# 05B-001.net
KiCad netlist of a schematic drawn in EAGLE
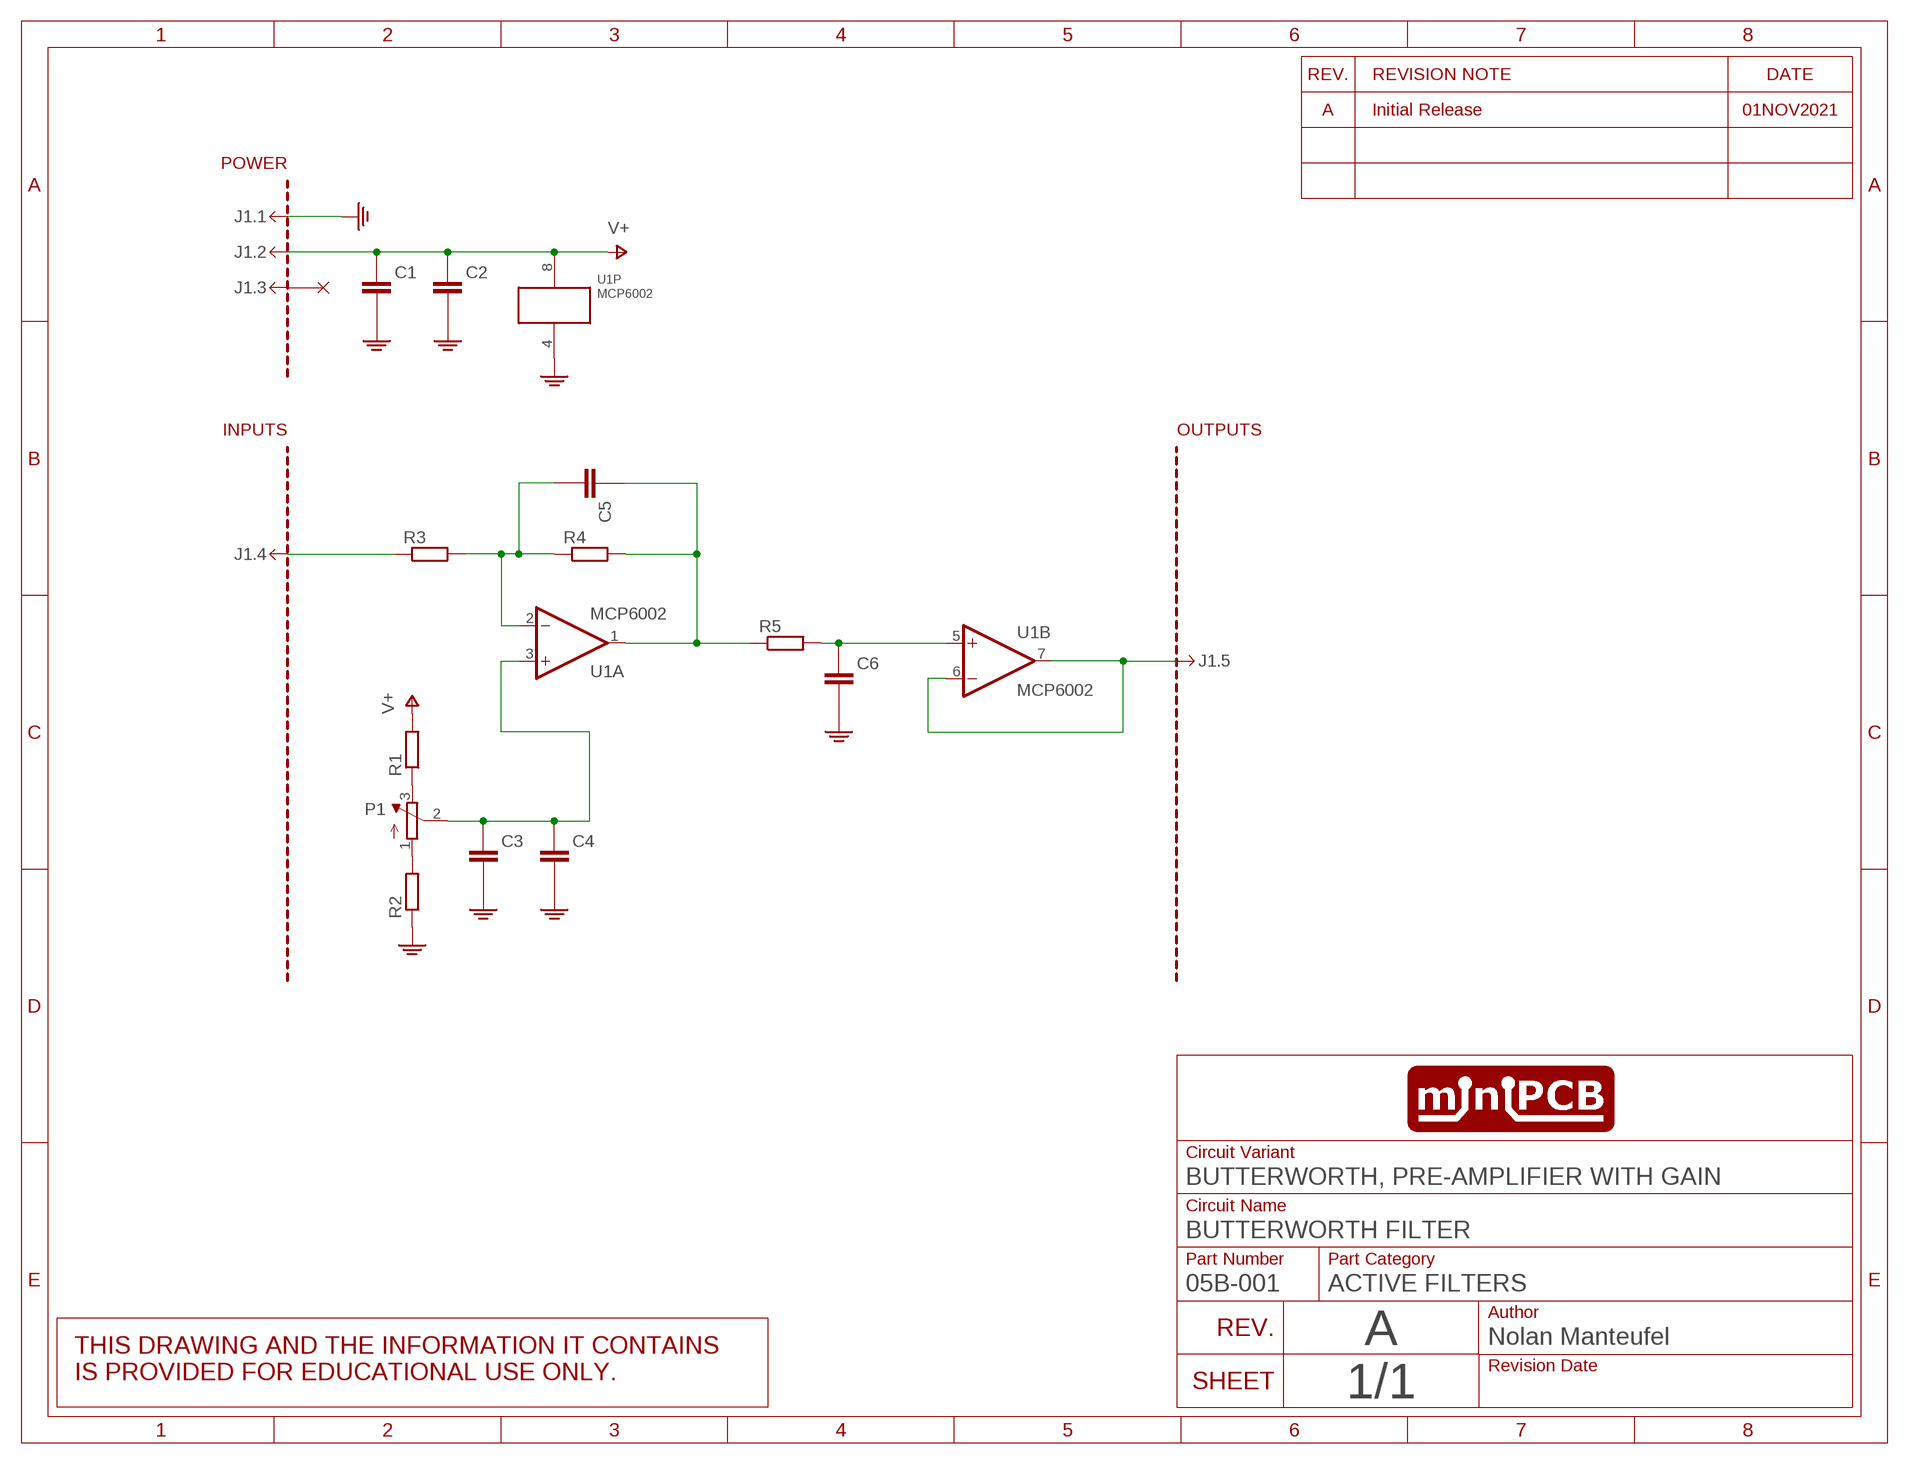
[diagram p0: schematic, sheet 1]

(export (version "E")
  (design (tool "Eeschema 10.0.6"))
  (components
    (comp (ref "C1")
      (value "CAPACITORSMD")
      (footprint "eagle-import:C0805")
      (libsource (lib "eagle-import") (part "CAPACITORSMD"))
    )
    (comp (ref "C2")
      (value "CAPACITORSMD")
      (footprint "eagle-import:C0805")
      (libsource (lib "eagle-import") (part "CAPACITORSMD"))
    )
    (comp (ref "C3")
      (value "CAPACITORSMD")
      (footprint "eagle-import:C0805")
      (libsource (lib "eagle-import") (part "CAPACITORSMD"))
    )
    (comp (ref "C4")
      (value "CAPACITORSMD")
      (footprint "eagle-import:C0805")
      (libsource (lib "eagle-import") (part "CAPACITORSMD"))
    )
    (comp (ref "C5")
      (value "CAPACITORSMD")
      (footprint "eagle-import:C0805")
      (libsource (lib "eagle-import") (part "CAPACITORSMD"))
    )
    (comp (ref "C6")
      (value "CAPACITORSMD")
      (footprint "eagle-import:C0805")
      (libsource (lib "eagle-import") (part "CAPACITORSMD"))
    )
    (comp (ref "J1.")
      (value "MINIPCB_5P20X15")
      (footprint "eagle-import:MINIPCB_5P_20X15MM")
      (fields (field (name "PART_NUMBER") "05B-001"))
      (libsource (lib "eagle-import") (part "MINIPCB_5P20X15"))
    )
    (comp (ref "P1")
      (value "TRIMPOT0.100THD")
      (footprint "eagle-import:TRIM_0100")
      (libsource (lib "eagle-import") (part "TRIMPOT0.100THD"))
    )
    (comp (ref "R1")
      (value "RESISTORSMD")
      (footprint "eagle-import:R0805")
      (libsource (lib "eagle-import") (part "RESISTORSMD"))
    )
    (comp (ref "R2")
      (value "RESISTORSMD")
      (footprint "eagle-import:R0805")
      (libsource (lib "eagle-import") (part "RESISTORSMD"))
    )
    (comp (ref "R3")
      (value "RESISTORSMD")
      (footprint "eagle-import:R0805")
      (libsource (lib "eagle-import") (part "RESISTORSMD"))
    )
    (comp (ref "R4")
      (value "RESISTORSMD")
      (footprint "eagle-import:R0805")
      (libsource (lib "eagle-import") (part "RESISTORSMD"))
    )
    (comp (ref "R5")
      (value "RESISTORSMD")
      (footprint "eagle-import:R0805")
      (libsource (lib "eagle-import") (part "RESISTORSMD"))
    )
    (comp (ref "U1")
      (value "MCP6002")
      (footprint "eagle-import:SO08")
      (libsource (lib "eagle-import") (part "OPAMP_DUALSMD"))
    )
  )
  (nets
    (net (code "1") (name "GND") (class "Default")
      (node (ref "C1") (pin "2") (pinfunction "-_2") (pintype "passive"))
      (node (ref "C2") (pin "2") (pinfunction "-_2") (pintype "passive"))
      (node (ref "C3") (pin "2") (pinfunction "-_2") (pintype "passive"))
      (node (ref "C4") (pin "2") (pinfunction "-_2") (pintype "passive"))
      (node (ref "C6") (pin "2") (pinfunction "-_2") (pintype "passive"))
      (node (ref "J1.") (pin "1") (pinfunction "1_1") (pintype "bidirectional"))
      (node (ref "R2") (pin "1") (pinfunction "1_1") (pintype "passive"))
      (node (ref "U1") (pin "4") (pinfunction "V-_4") (pintype "power_in"))
    )
    (net (code "2") (name "Net-(C3-+)") (class "Default")
      (node (ref "C3") (pin "1") (pinfunction "+_1") (pintype "passive"))
      (node (ref "C4") (pin "1") (pinfunction "+_1") (pintype "passive"))
      (node (ref "P1") (pin "2") (pinfunction "S_2") (pintype "passive"))
      (node (ref "U1") (pin "3") (pinfunction "+IN_3") (pintype "input"))
    )
    (net (code "3") (name "Net-(C5-+)") (class "Default")
      (node (ref "C5") (pin "1") (pinfunction "+_1") (pintype "passive"))
      (node (ref "R4") (pin "2") (pinfunction "2_2") (pintype "passive"))
      (node (ref "R5") (pin "1") (pinfunction "1_1") (pintype "passive"))
      (node (ref "U1") (pin "1") (pinfunction "OUT_1") (pintype "output"))
    )
    (net (code "4") (name "Net-(C5--)") (class "Default")
      (node (ref "C5") (pin "2") (pinfunction "-_2") (pintype "passive"))
      (node (ref "R3") (pin "2") (pinfunction "2_2") (pintype "passive"))
      (node (ref "R4") (pin "1") (pinfunction "1_1") (pintype "passive"))
      (node (ref "U1") (pin "2") (pinfunction "-IN_2") (pintype "input"))
    )
    (net (code "5") (name "Net-(C6-+)") (class "Default")
      (node (ref "C6") (pin "1") (pinfunction "+_1") (pintype "passive"))
      (node (ref "R5") (pin "2") (pinfunction "2_2") (pintype "passive"))
      (node (ref "U1") (pin "5") (pinfunction "+IN_5") (pintype "input"))
    )
    (net (code "6") (name "Net-(J1.D-1)") (class "Default")
      (node (ref "J1.") (pin "4") (pinfunction "1_4") (pintype "bidirectional"))
      (node (ref "R3") (pin "1") (pinfunction "1_1") (pintype "passive"))
    )
    (net (code "7") (name "Net-(J1.H-1)") (class "Default")
      (node (ref "J1.") (pin "5") (pinfunction "1_5") (pintype "bidirectional"))
      (node (ref "U1") (pin "6") (pinfunction "-IN_6") (pintype "input"))
      (node (ref "U1") (pin "7") (pinfunction "OUT_7") (pintype "output"))
    )
    (net (code "8") (name "Net-(P1-A)") (class "Default")
      (node (ref "P1") (pin "1") (pinfunction "A_1") (pintype "passive"))
      (node (ref "R2") (pin "2") (pinfunction "2_2") (pintype "passive"))
    )
    (net (code "9") (name "Net-(P1-E)") (class "Default")
      (node (ref "P1") (pin "3") (pinfunction "E_3") (pintype "passive"))
      (node (ref "R1") (pin "1") (pinfunction "1_1") (pintype "passive"))
    )
    (net (code "10") (name "V+") (class "Default")
      (node (ref "C1") (pin "1") (pinfunction "+_1") (pintype "passive"))
      (node (ref "C2") (pin "1") (pinfunction "+_1") (pintype "passive"))
      (node (ref "J1.") (pin "2") (pinfunction "1_2") (pintype "bidirectional"))
      (node (ref "R1") (pin "2") (pinfunction "2_2") (pintype "passive"))
      (node (ref "U1") (pin "8") (pinfunction "V+_8") (pintype "power_in"))
    )
    (net (code "11") (name "unconnected-(J1.C-1-Pad3)") (class "Default")
      (node (ref "J1.") (pin "3") (pinfunction "1_3") (pintype "bidirectional"))
    )
  )
)
